# ISO.net
KiCad netlist of a schematic drawn in Altium Designer
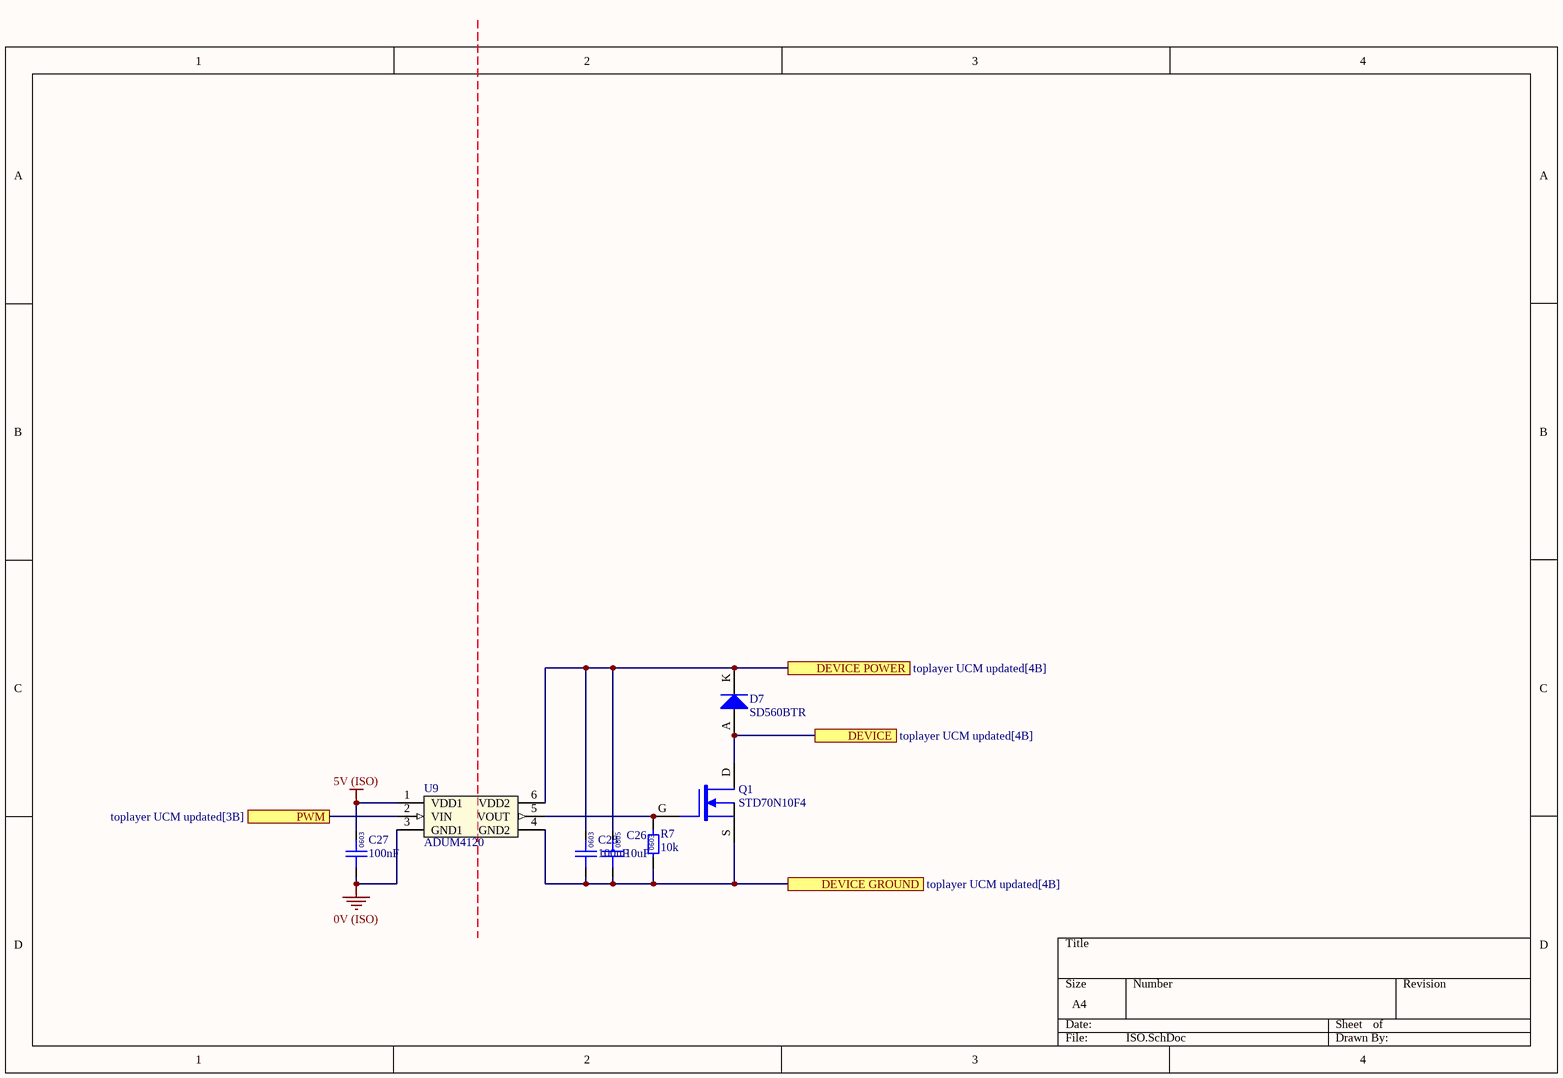
[diagram p0: ISO.SchDoc]

(export (version "E")
  (design (tool "Eeschema 10.0.6"))
  (components
    (comp (ref "C26")
      (value "10uF")
      (footprint "0805")
      (fields
        (field (name "PART NUMBER") "GRM21BR6YA106KE43L")
        (field (name "MANUFACTURER") "muRata")
        (field (name "TOLERANCE") "10%")
      )
      (libsource (lib "ts_standard_library") (part "Capacitor 0805"))
    )
    (comp (ref "C27")
      (value "100nF")
      (footprint "0603")
      (fields
        (field (name "PART NUMBER") "GCM188L81H104KA57D")
        (field (name "MANUFACTURER") "muRata")
        (field (name "TOLERANCE") "±10%")
      )
      (libsource (lib "ts_standard_library") (part "Capacitor 0603"))
    )
    (comp (ref "C28")
      (value "100nF")
      (footprint "0603")
      (fields
        (field (name "PART NUMBER") "GCM188L81H104KA57D")
        (field (name "MANUFACTURER") "muRata")
        (field (name "TOLERANCE") "±10%")
      )
      (libsource (lib "ts_standard_library") (part "Capacitor 0603"))
    )
    (comp (ref "D7")
      (value "SD560BTR")
      (footprint "SMB Diode")
      (description "1.2V_F 600V 5A SMB")
      (fields
        (field (name "MANUFACTURER") "SMC Diode Solutions")
        (field (name "DIGIKEY PART NUMBER") "1655-1530-2-ND")
      )
      (libsource (lib "ts_20-standard-library") (part "Diode"))
    )
    (comp (ref "Q1")
      (value "STD70N10F4")
      (footprint "STM TO-252 MOSFET")
      (description "N-Channel 100V 60A (Tc) 125W (Tc) Surface Mount DPAK")
      (fields
        (field (name "MANUFACTURER") "STMicroelectronics")
        (field (name "DIGIKEY PART NUMBER") "497-8806-2-ND")
        (field (name "PUBLISHER") "Altium Limited")
      )
      (libsource (lib "ts_20-standard-library") (part "MOSFET-N"))
    )
    (comp (ref "R7")
      (value "10k")
      (footprint "0603")
      (fields
        (field (name "PART NUMBER") "RC0603FR-0710KL")
        (field (name "MANUFACTURER") "YAGEO")
        (field (name "TOLERANCE") "0.01")
      )
      (libsource (lib "ts_standard_library") (part "Resistor 0603"))
    )
    (comp (ref "U9")
      (value "ADUM4120")
      (footprint "AD 6-SOIC")
      (description "DGTL ISO 5KV 1CH GATE DRVR 6SOIC")
      (fields
        (field (name "MANUFACTURER") "Analogue Devices")
        (field (name "DIGIKEY PART NUMBER") "ADUM4120-1ARIZ-ND")
      )
      (libsource (lib "ts_20-standard-library") (part "ADUM4120"))
    )
  )
  (nets
    (net (code "1") (name "/DEVICE") (class "Default")
      (node (ref "D7") (pin "A") (pinfunction "A_A") (pintype "passive"))
      (node (ref "Q1") (pin "D") (pinfunction "D_D") (pintype "passive"))
    )
    (net (code "2") (name "/DEVICE GROUND") (class "Default")
      (node (ref "C26") (pin "1") (pinfunction "1_1") (pintype "passive"))
      (node (ref "C28") (pin "1") (pinfunction "1_1") (pintype "passive"))
      (node (ref "Q1") (pin "S") (pinfunction "S_S") (pintype "passive"))
      (node (ref "R7") (pin "1") (pinfunction "1_1") (pintype "passive"))
      (node (ref "U9") (pin "4") (pinfunction "GND2_4") (pintype "power_in"))
    )
    (net (code "3") (name "/DEVICE POWER") (class "Default")
      (node (ref "C26") (pin "2") (pinfunction "2_2") (pintype "passive"))
      (node (ref "C28") (pin "2") (pinfunction "2_2") (pintype "passive"))
      (node (ref "D7") (pin "K") (pinfunction "K_K") (pintype "passive"))
      (node (ref "U9") (pin "6") (pinfunction "VDD2_6") (pintype "power_in"))
    )
    (net (code "4") (name "/PWM") (class "Default")
      (node (ref "U9") (pin "2") (pinfunction "VIN_2") (pintype "input"))
    )
    (net (code "5") (name "0V (ISO)") (class "Default")
      (node (ref "C27") (pin "1") (pinfunction "1_1") (pintype "passive"))
      (node (ref "U9") (pin "3") (pinfunction "GND1_3") (pintype "power_in"))
    )
    (net (code "6") (name "5V (ISO)") (class "Default")
      (node (ref "C27") (pin "2") (pinfunction "2_2") (pintype "passive"))
      (node (ref "U9") (pin "1") (pinfunction "VDD1_1") (pintype "power_in"))
    )
    (net (code "7") (name "Net-(U9-VOUT)") (class "Default")
      (node (ref "Q1") (pin "G") (pinfunction "G_G") (pintype "passive"))
      (node (ref "R7") (pin "2") (pinfunction "2_2") (pintype "passive"))
      (node (ref "U9") (pin "5") (pinfunction "VOUT_5") (pintype "output"))
    )
  )
)
